# MainboardConn.net
KiCad netlist of a schematic drawn in Altium Designer
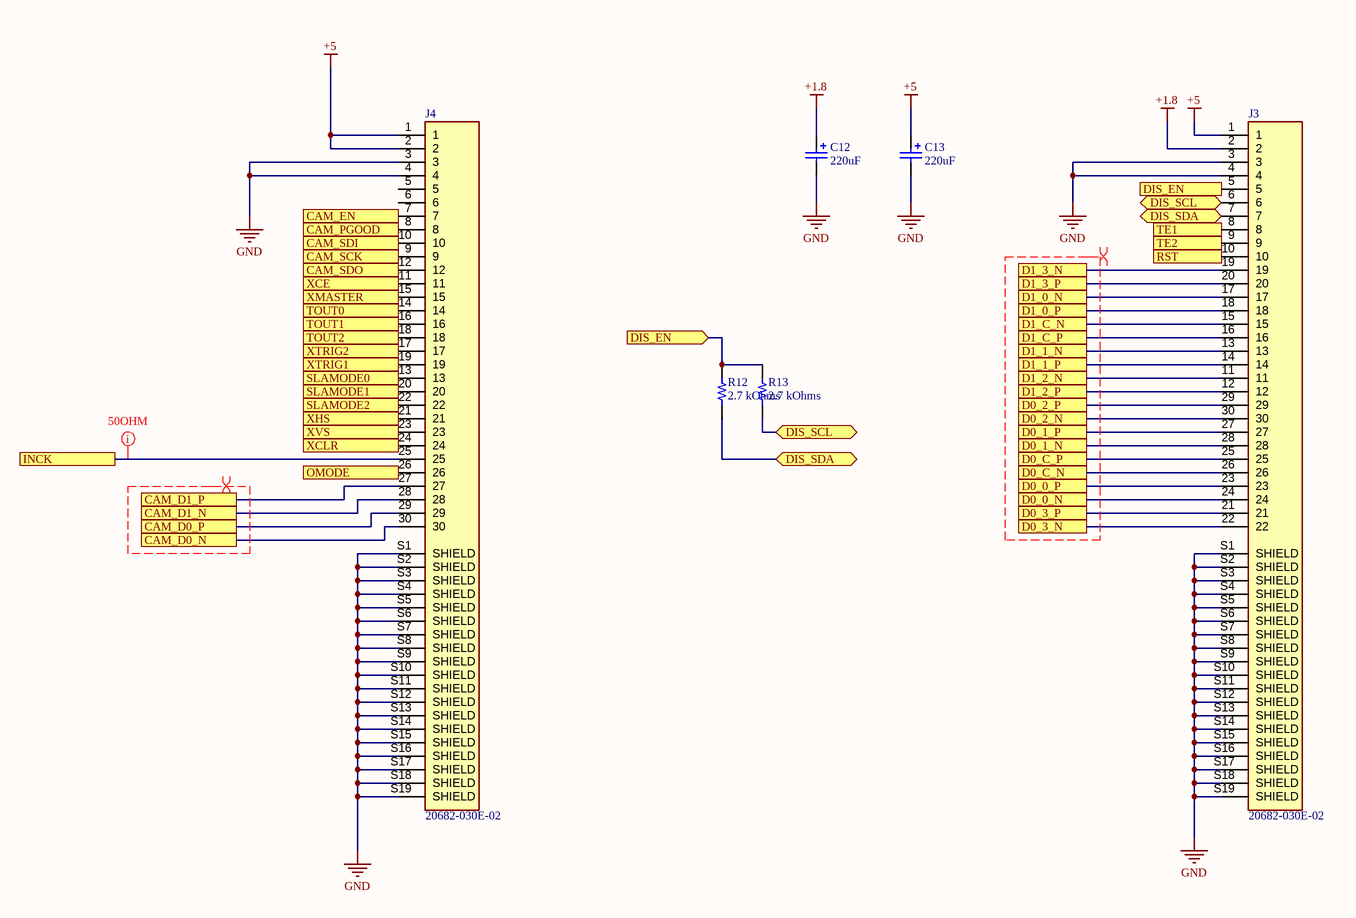
[diagram p0: MainboardConn.SchDoc]

(export (version "E")
  (design (tool "Eeschema 10.0.6"))
  (components
    (comp (ref "C12")
      (value "220uF")
      (footprint "WCAP-PHGP_L7.3W4.3H1.9")
      (description "WCAP-PHGP Aluminum Polymer Capacitor, H-Chip SMT, L7.3W4.3H1.9mm, 220uF, 6.3V")
      (fields
        (field (name "MANUFACTURER") "Wurth Elektronik")
        (field (name "MANUFACTURER PART NUMBER") "875015119006")
      )
      (libsource (lib "Altium_WCAP-PHGP (rev22a)") (part "875015119006"))
    )
    (comp (ref "C13")
      (value "220uF")
      (footprint "WCAP-PHGP_L7.3W4.3H1.9")
      (description "WCAP-PHGP Aluminum Polymer Capacitor, H-Chip SMT, L7.3W4.3H1.9mm, 220uF, 6.3V")
      (fields
        (field (name "MANUFACTURER") "Wurth Elektronik")
        (field (name "MANUFACTURER PART NUMBER") "875015119006")
      )
      (libsource (lib "Altium_WCAP-PHGP (rev22a)") (part "875015119006"))
    )
    (comp (ref "J3")
      (value "20682-030E-02")
      (footprint "20682-030E-02:IPEX_20682-030E-02")
      (description "Cabline-CAII Rece. Ass'y")
      (fields (field (name "MF") "{'manufacturer': u'I-PEX'}"))
      (libsource (lib "*") (part "20682-030E-02"))
    )
    (comp (ref "J4")
      (value "20682-030E-02")
      (footprint "IPEX_20682-030E-02")
      (description "Cabline-CAII Rece. Ass'y")
      (fields (field (name "MF") "{'manufacturer': u'I-PEX'}"))
      (libsource (lib "SimulaVR") (part "20682-030E-02"))
    )
    (comp (ref "R12")
      (value "2.7 kOhms")
      (footprint "RES 0201_0603")
      (description "RES 2.7K OHM 5% 1/20W 0201 SMD")
      (fields
        (field (name "PART NUMBER") "ERJ-U01J272C")
        (field (name "MANUFACTURER") "Panasonic Electronic Components")
      )
      (libsource (lib "Celestial Altium Library - altium_library") (part "Resistor"))
    )
    (comp (ref "R13")
      (value "2.7 kOhms")
      (footprint "RES 0201_0603")
      (description "RES 2.7K OHM 5% 1/20W 0201 SMD")
      (fields
        (field (name "PART NUMBER") "ERJ-U01J272C")
        (field (name "MANUFACTURER") "Panasonic Electronic Components")
      )
      (libsource (lib "Celestial Altium Library - altium_library") (part "Resistor"))
    )
  )
  (nets
    (net (code "1") (name "+1.8") (class "Default")
      (node (ref "C12") (pin "1") (pinfunction "P_1") (pintype "passive"))
      (node (ref "J3") (pin "2") (pinfunction "2_2") (pintype "passive"))
    )
    (net (code "2") (name "+5") (class "Default")
      (node (ref "C13") (pin "1") (pinfunction "P_1") (pintype "passive"))
      (node (ref "J3") (pin "1") (pinfunction "1_1") (pintype "passive"))
      (node (ref "J4") (pin "1") (pinfunction "1_1") (pintype "passive"))
      (node (ref "J4") (pin "2") (pinfunction "2_2") (pintype "passive"))
    )
    (net (code "3") (name "/CAM_D0_N") (class "Default")
      (node (ref "J4") (pin "30") (pinfunction "30_30") (pintype "passive"))
    )
    (net (code "4") (name "/CAM_D0_P") (class "Default")
      (node (ref "J4") (pin "29") (pinfunction "29_29") (pintype "passive"))
    )
    (net (code "5") (name "/CAM_D1_N") (class "Default")
      (node (ref "J4") (pin "28") (pinfunction "28_28") (pintype "passive"))
    )
    (net (code "6") (name "/CAM_D1_P") (class "Default")
      (node (ref "J4") (pin "27") (pinfunction "27_27") (pintype "passive"))
    )
    (net (code "7") (name "/CAM_EN") (class "Default")
      (node (ref "J4") (pin "7") (pinfunction "7_7") (pintype "passive"))
    )
    (net (code "8") (name "/CAM_PGOOD") (class "Default")
      (node (ref "J4") (pin "8") (pinfunction "8_8") (pintype "passive"))
    )
    (net (code "9") (name "/CAM_SCK") (class "Default")
      (node (ref "J4") (pin "9") (pinfunction "9_9") (pintype "passive"))
    )
    (net (code "10") (name "/CAM_SDI") (class "Default")
      (node (ref "J4") (pin "10") (pinfunction "10_10") (pintype "passive"))
    )
    (net (code "11") (name "/CAM_SDO") (class "Default")
      (node (ref "J4") (pin "12") (pinfunction "12_12") (pintype "passive"))
    )
    (net (code "12") (name "/D0_0_N") (class "Default")
      (node (ref "J3") (pin "24") (pinfunction "24_24") (pintype "passive"))
    )
    (net (code "13") (name "/D0_0_P") (class "Default")
      (node (ref "J3") (pin "23") (pinfunction "23_23") (pintype "passive"))
    )
    (net (code "14") (name "/D0_1_N") (class "Default")
      (node (ref "J3") (pin "28") (pinfunction "28_28") (pintype "passive"))
    )
    (net (code "15") (name "/D0_1_P") (class "Default")
      (node (ref "J3") (pin "27") (pinfunction "27_27") (pintype "passive"))
    )
    (net (code "16") (name "/D0_2_N") (class "Default")
      (node (ref "J3") (pin "30") (pinfunction "30_30") (pintype "passive"))
    )
    (net (code "17") (name "/D0_2_P") (class "Default")
      (node (ref "J3") (pin "29") (pinfunction "29_29") (pintype "passive"))
    )
    (net (code "18") (name "/D0_3_N") (class "Default")
      (node (ref "J3") (pin "22") (pinfunction "22_22") (pintype "passive"))
    )
    (net (code "19") (name "/D0_3_P") (class "Default")
      (node (ref "J3") (pin "21") (pinfunction "21_21") (pintype "passive"))
    )
    (net (code "20") (name "/D0_C_N") (class "Default")
      (node (ref "J3") (pin "26") (pinfunction "26_26") (pintype "passive"))
    )
    (net (code "21") (name "/D0_C_P") (class "Default")
      (node (ref "J3") (pin "25") (pinfunction "25_25") (pintype "passive"))
    )
    (net (code "22") (name "/D1_0_N") (class "Default")
      (node (ref "J3") (pin "17") (pinfunction "17_17") (pintype "passive"))
    )
    (net (code "23") (name "/D1_0_P") (class "Default")
      (node (ref "J3") (pin "18") (pinfunction "18_18") (pintype "passive"))
    )
    (net (code "24") (name "/D1_1_N") (class "Default")
      (node (ref "J3") (pin "13") (pinfunction "13_13") (pintype "passive"))
    )
    (net (code "25") (name "/D1_1_P") (class "Default")
      (node (ref "J3") (pin "14") (pinfunction "14_14") (pintype "passive"))
    )
    (net (code "26") (name "/D1_2_N") (class "Default")
      (node (ref "J3") (pin "11") (pinfunction "11_11") (pintype "passive"))
    )
    (net (code "27") (name "/D1_2_P") (class "Default")
      (node (ref "J3") (pin "12") (pinfunction "12_12") (pintype "passive"))
    )
    (net (code "28") (name "/D1_3_N") (class "Default")
      (node (ref "J3") (pin "19") (pinfunction "19_19") (pintype "passive"))
    )
    (net (code "29") (name "/D1_3_P") (class "Default")
      (node (ref "J3") (pin "20") (pinfunction "20_20") (pintype "passive"))
    )
    (net (code "30") (name "/D1_C_N") (class "Default")
      (node (ref "J3") (pin "15") (pinfunction "15_15") (pintype "passive"))
    )
    (net (code "31") (name "/D1_C_P") (class "Default")
      (node (ref "J3") (pin "16") (pinfunction "16_16") (pintype "passive"))
    )
    (net (code "32") (name "/DIS_EN") (class "Default")
      (node (ref "J3") (pin "5") (pinfunction "5_5") (pintype "passive"))
      (node (ref "R12") (pin "2") (pinfunction "2_2") (pintype "passive"))
      (node (ref "R13") (pin "2") (pinfunction "2_2") (pintype "passive"))
    )
    (net (code "33") (name "/DIS_SCL") (class "Default")
      (node (ref "J3") (pin "6") (pinfunction "6_6") (pintype "passive"))
      (node (ref "R13") (pin "1") (pinfunction "1_1") (pintype "passive"))
    )
    (net (code "34") (name "/DIS_SDA") (class "Default")
      (node (ref "J3") (pin "7") (pinfunction "7_7") (pintype "passive"))
      (node (ref "R12") (pin "1") (pinfunction "1_1") (pintype "passive"))
    )
    (net (code "35") (name "/INCK") (class "Default")
      (node (ref "J4") (pin "25") (pinfunction "25_25") (pintype "passive"))
    )
    (net (code "36") (name "/OMODE") (class "Default")
      (node (ref "J4") (pin "26") (pinfunction "26_26") (pintype "passive"))
    )
    (net (code "37") (name "/RST") (class "Default")
      (node (ref "J3") (pin "10") (pinfunction "10_10") (pintype "passive"))
    )
    (net (code "38") (name "/SLAMODE0") (class "Default")
      (node (ref "J4") (pin "13") (pinfunction "13_13") (pintype "passive"))
    )
    (net (code "39") (name "/SLAMODE1") (class "Default")
      (node (ref "J4") (pin "20") (pinfunction "20_20") (pintype "passive"))
    )
    (net (code "40") (name "/SLAMODE2") (class "Default")
      (node (ref "J4") (pin "22") (pinfunction "22_22") (pintype "passive"))
    )
    (net (code "41") (name "/TE1") (class "Default")
      (node (ref "J3") (pin "8") (pinfunction "8_8") (pintype "passive"))
    )
    (net (code "42") (name "/TE2") (class "Default")
      (node (ref "J3") (pin "9") (pinfunction "9_9") (pintype "passive"))
    )
    (net (code "43") (name "/TOUT0") (class "Default")
      (node (ref "J4") (pin "14") (pinfunction "14_14") (pintype "passive"))
    )
    (net (code "44") (name "/TOUT1") (class "Default")
      (node (ref "J4") (pin "16") (pinfunction "16_16") (pintype "passive"))
    )
    (net (code "45") (name "/TOUT2") (class "Default")
      (node (ref "J4") (pin "18") (pinfunction "18_18") (pintype "passive"))
    )
    (net (code "46") (name "/XCE") (class "Default")
      (node (ref "J4") (pin "11") (pinfunction "11_11") (pintype "passive"))
    )
    (net (code "47") (name "/XCLR") (class "Default")
      (node (ref "J4") (pin "24") (pinfunction "24_24") (pintype "passive"))
    )
    (net (code "48") (name "/XHS") (class "Default")
      (node (ref "J4") (pin "21") (pinfunction "21_21") (pintype "passive"))
    )
    (net (code "49") (name "/XMASTER") (class "Default")
      (node (ref "J4") (pin "15") (pinfunction "15_15") (pintype "passive"))
    )
    (net (code "50") (name "/XTRIG1") (class "Default")
      (node (ref "J4") (pin "19") (pinfunction "19_19") (pintype "passive"))
    )
    (net (code "51") (name "/XTRIG2") (class "Default")
      (node (ref "J4") (pin "17") (pinfunction "17_17") (pintype "passive"))
    )
    (net (code "52") (name "/XVS") (class "Default")
      (node (ref "J4") (pin "23") (pinfunction "23_23") (pintype "passive"))
    )
    (net (code "53") (name "GND") (class "Default")
      (node (ref "C12") (pin "2") (pinfunction "N_2") (pintype "passive"))
      (node (ref "C13") (pin "2") (pinfunction "N_2") (pintype "passive"))
      (node (ref "J3") (pin "3") (pinfunction "3_3") (pintype "passive"))
      (node (ref "J3") (pin "4") (pinfunction "4_4") (pintype "passive"))
      (node (ref "J3") (pin "S1") (pinfunction "SHIELD_S1") (pintype "passive"))
      (node (ref "J3") (pin "S10") (pinfunction "SHIELD_S10") (pintype "passive"))
      (node (ref "J3") (pin "S11") (pinfunction "SHIELD_S11") (pintype "passive"))
      (node (ref "J3") (pin "S12") (pinfunction "SHIELD_S12") (pintype "passive"))
      (node (ref "J3") (pin "S13") (pinfunction "SHIELD_S13") (pintype "passive"))
      (node (ref "J3") (pin "S14") (pinfunction "SHIELD_S14") (pintype "passive"))
      (node (ref "J3") (pin "S15") (pinfunction "SHIELD_S15") (pintype "passive"))
      (node (ref "J3") (pin "S16") (pinfunction "SHIELD_S16") (pintype "passive"))
      (node (ref "J3") (pin "S17") (pinfunction "SHIELD_S17") (pintype "passive"))
      (node (ref "J3") (pin "S18") (pinfunction "SHIELD_S18") (pintype "passive"))
      (node (ref "J3") (pin "S19") (pinfunction "SHIELD_S19") (pintype "passive"))
      (node (ref "J3") (pin "S2") (pinfunction "SHIELD_S2") (pintype "passive"))
      (node (ref "J3") (pin "S3") (pinfunction "SHIELD_S3") (pintype "passive"))
      (node (ref "J3") (pin "S4") (pinfunction "SHIELD_S4") (pintype "passive"))
      (node (ref "J3") (pin "S5") (pinfunction "SHIELD_S5") (pintype "passive"))
      (node (ref "J3") (pin "S6") (pinfunction "SHIELD_S6") (pintype "passive"))
      (node (ref "J3") (pin "S7") (pinfunction "SHIELD_S7") (pintype "passive"))
      (node (ref "J3") (pin "S8") (pinfunction "SHIELD_S8") (pintype "passive"))
      (node (ref "J3") (pin "S9") (pinfunction "SHIELD_S9") (pintype "passive"))
      (node (ref "J4") (pin "3") (pinfunction "3_3") (pintype "passive"))
      (node (ref "J4") (pin "4") (pinfunction "4_4") (pintype "passive"))
      (node (ref "J4") (pin "S1") (pinfunction "SHIELD_S1") (pintype "passive"))
      (node (ref "J4") (pin "S10") (pinfunction "SHIELD_S10") (pintype "passive"))
      (node (ref "J4") (pin "S11") (pinfunction "SHIELD_S11") (pintype "passive"))
      (node (ref "J4") (pin "S12") (pinfunction "SHIELD_S12") (pintype "passive"))
      (node (ref "J4") (pin "S13") (pinfunction "SHIELD_S13") (pintype "passive"))
      (node (ref "J4") (pin "S14") (pinfunction "SHIELD_S14") (pintype "passive"))
      (node (ref "J4") (pin "S15") (pinfunction "SHIELD_S15") (pintype "passive"))
      (node (ref "J4") (pin "S16") (pinfunction "SHIELD_S16") (pintype "passive"))
      (node (ref "J4") (pin "S17") (pinfunction "SHIELD_S17") (pintype "passive"))
      (node (ref "J4") (pin "S18") (pinfunction "SHIELD_S18") (pintype "passive"))
      (node (ref "J4") (pin "S19") (pinfunction "SHIELD_S19") (pintype "passive"))
      (node (ref "J4") (pin "S2") (pinfunction "SHIELD_S2") (pintype "passive"))
      (node (ref "J4") (pin "S3") (pinfunction "SHIELD_S3") (pintype "passive"))
      (node (ref "J4") (pin "S4") (pinfunction "SHIELD_S4") (pintype "passive"))
      (node (ref "J4") (pin "S5") (pinfunction "SHIELD_S5") (pintype "passive"))
      (node (ref "J4") (pin "S6") (pinfunction "SHIELD_S6") (pintype "passive"))
      (node (ref "J4") (pin "S7") (pinfunction "SHIELD_S7") (pintype "passive"))
      (node (ref "J4") (pin "S8") (pinfunction "SHIELD_S8") (pintype "passive"))
      (node (ref "J4") (pin "S9") (pinfunction "SHIELD_S9") (pintype "passive"))
    )
    (net (code "54") (name "unconnected-(J4-Pad5)") (class "Default")
      (node (ref "J4") (pin "5") (pinfunction "5_5") (pintype "passive"))
    )
    (net (code "55") (name "unconnected-(J4-Pad6)") (class "Default")
      (node (ref "J4") (pin "6") (pinfunction "6_6") (pintype "passive"))
    )
  )
)
